# POWER.net
KiCad netlist of a schematic drawn in Altium Designer
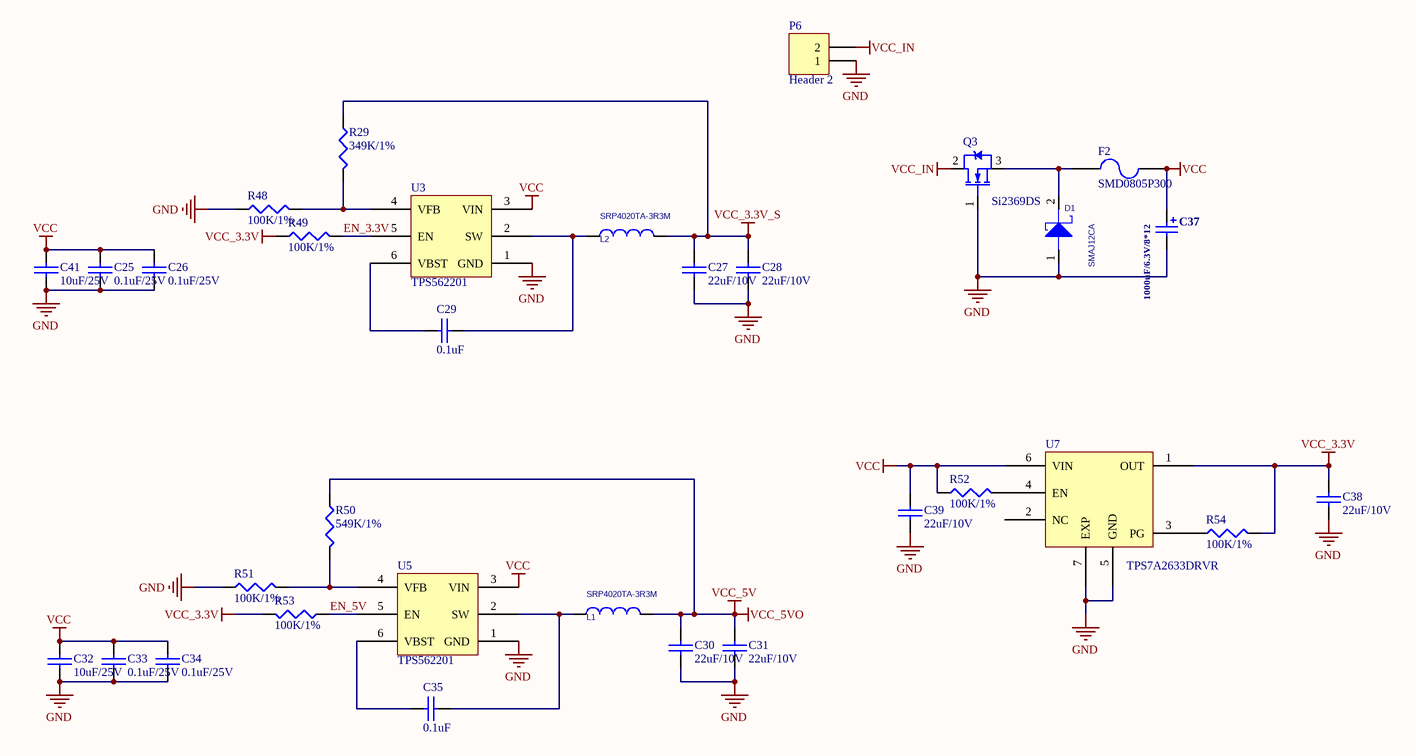
[diagram p0: POWER.SchDoc]

(export (version "E")
  (design (tool "Eeschema 10.0.6"))
  (components
    (comp (ref "C25")
      (value "0.1uF/25V")
      (footprint "0603C")
      (description "Capacitor")
      (libsource (lib "ZWLIntegrated_Library") (part "CAP"))
    )
    (comp (ref "C26")
      (value "0.1uF/25V")
      (footprint "0603C")
      (description "Capacitor")
      (libsource (lib "ZWLIntegrated_Library") (part "CAP"))
    )
    (comp (ref "C27")
      (value "22uF/10V")
      (footprint "1206C")
      (description "Capacitor")
      (libsource (lib "ZWLIntegrated_Library") (part "CAP"))
    )
    (comp (ref "C28")
      (value "22uF/10V")
      (footprint "1206C")
      (description "Capacitor")
      (libsource (lib "ZWLIntegrated_Library") (part "CAP"))
    )
    (comp (ref "C29")
      (value "0.1uF")
      (footprint "0603C")
      (description "Capacitor")
      (libsource (lib "ZWLIntegrated_Library") (part "CAP"))
    )
    (comp (ref "C30")
      (value "22uF/10V")
      (footprint "1206C")
      (description "Capacitor")
      (libsource (lib "ZWLIntegrated_Library") (part "CAP"))
    )
    (comp (ref "C31")
      (value "22uF/10V")
      (footprint "1206C")
      (description "Capacitor")
      (libsource (lib "ZWLIntegrated_Library") (part "CAP"))
    )
    (comp (ref "C32")
      (value "10uF/25V")
      (footprint "0603C")
      (description "Capacitor")
      (libsource (lib "ZWLIntegrated_Library") (part "CAP"))
    )
    (comp (ref "C33")
      (value "0.1uF/25V")
      (footprint "0603C")
      (description "Capacitor")
      (libsource (lib "ZWLIntegrated_Library") (part "CAP"))
    )
    (comp (ref "C34")
      (value "0.1uF/25V")
      (footprint "0603C")
      (description "Capacitor")
      (libsource (lib "ZWLIntegrated_Library") (part "CAP"))
    )
    (comp (ref "C35")
      (value "0.1uF")
      (footprint "0603C")
      (description "Capacitor")
      (libsource (lib "ZWLIntegrated_Library") (part "CAP"))
    )
    (comp (ref "C37")
      (value "1000uF/6.3V/8*12")
      (footprint "8*12")
      (description "Polarized Capacitor (Surface Mount)")
      (libsource (lib "KT_iBeacon") (part "Cap Pol3"))
    )
    (comp (ref "C38")
      (value "22uF/10V")
      (footprint "1206C")
      (description "Capacitor")
      (libsource (lib "ZWLIntegrated_Library") (part "CAP"))
    )
    (comp (ref "C39")
      (value "22uF/10V")
      (footprint "1206C")
      (description "Capacitor")
      (libsource (lib "ZWLIntegrated_Library") (part "CAP"))
    )
    (comp (ref "C41")
      (value "10uF/25V")
      (footprint "0603C")
      (description "Capacitor")
      (libsource (lib "ZWLIntegrated_Library") (part "CAP"))
    )
    (comp (ref "D1")
      (value "SMAJ12CA")
      (footprint "SMA")
      (libsource (lib "KT_iBeacon") (part "DIODE_SCHOTTKY_0"))
    )
    (comp (ref "F2")
      (value "SMD0805P300")
      (footprint "0805R")
      (description "Fuse")
      (fields (field (name "PUBLISHER") "Altium Limited"))
      (libsource (lib "Miscellaneous Devices") (part "Fuse 2"))
    )
    (comp (ref "L1") (value "SRP4020TA-3R3M") (footprint "CD_4*4") (libsource (lib "*") (part "INDUCTOR_1")))
    (comp (ref "L2") (value "SRP4020TA-3R3M") (footprint "CD_4*4") (libsource (lib "*") (part "INDUCTOR_1")))
    (comp (ref "P6")
      (value "Header 2")
      (footprint "2X2.54MMZ")
      (description "Header, 2-Pin")
      (fields (field (name "PUBLISHER") "Altium Limited"))
      (libsource (lib "Miscellaneous Connectors") (part "Header 2"))
    )
    (comp (ref "Q3")
      (value "Si2369DS")
      (footprint "sot23-3")
      (description "NMOSFET")
      (libsource (lib "SM") (part "NCE4060K"))
    )
    (comp (ref "R29")
      (value "349K/1%")
      (footprint "0603R")
      (libsource (lib "ZWLIntegrated_Library") (part "RES1"))
    )
    (comp (ref "R48")
      (value "100K/1%")
      (footprint "0603R")
      (libsource (lib "ZWLIntegrated_Library") (part "RES1"))
    )
    (comp (ref "R49")
      (value "100K/1%")
      (footprint "0603R")
      (libsource (lib "ZWLIntegrated_Library") (part "RES1"))
    )
    (comp (ref "R50")
      (value "549K/1%")
      (footprint "0603R")
      (libsource (lib "ZWLIntegrated_Library") (part "RES1"))
    )
    (comp (ref "R51")
      (value "100K/1%")
      (footprint "0603R")
      (libsource (lib "ZWLIntegrated_Library") (part "RES1"))
    )
    (comp (ref "R52")
      (value "100K/1%")
      (footprint "0603R")
      (libsource (lib "ZWLIntegrated_Library") (part "RES1"))
    )
    (comp (ref "R53")
      (value "100K/1%")
      (footprint "0603R")
      (libsource (lib "ZWLIntegrated_Library") (part "RES1"))
    )
    (comp (ref "R54")
      (value "100K/1%")
      (footprint "0603R")
      (libsource (lib "ZWLIntegrated_Library") (part "RES1"))
    )
    (comp (ref "U3")
      (value "TPS562201")
      (footprint "SOT-23-6")
      (libsource (lib "Schlib_20110825") (part "TPS562201"))
    )
    (comp (ref "U5")
      (value "TPS562201")
      (footprint "SOT-23-6")
      (libsource (lib "Schlib_20110825") (part "TPS562201"))
    )
    (comp (ref "U7")
      (value "TPS7A2633DRVR")
      (footprint "WSON-6")
      (libsource (lib "stm32") (part "TPS7A2633DRVR"))
    )
  )
  (nets
    (net (code "1") (name "/EN_3.3V") (class "Default")
      (node (ref "R49") (pin "2") (pinfunction "2_2") (pintype "passive"))
      (node (ref "U3") (pin "5") (pinfunction "EN_5") (pintype "passive"))
    )
    (net (code "2") (name "/EN_5V") (class "Default")
      (node (ref "R53") (pin "1") (pinfunction "1_1") (pintype "passive"))
      (node (ref "U5") (pin "5") (pinfunction "EN_5") (pintype "passive"))
    )
    (net (code "3") (name "GND") (class "Default")
      (node (ref "C25") (pin "1") (pinfunction "1_1") (pintype "passive"))
      (node (ref "C26") (pin "1") (pinfunction "1_1") (pintype "passive"))
      (node (ref "C27") (pin "2") (pinfunction "2_2") (pintype "passive"))
      (node (ref "C28") (pin "2") (pinfunction "2_2") (pintype "passive"))
      (node (ref "C30") (pin "2") (pinfunction "2_2") (pintype "passive"))
      (node (ref "C31") (pin "2") (pinfunction "2_2") (pintype "passive"))
      (node (ref "C32") (pin "1") (pinfunction "1_1") (pintype "passive"))
      (node (ref "C33") (pin "1") (pinfunction "1_1") (pintype "passive"))
      (node (ref "C34") (pin "1") (pinfunction "1_1") (pintype "passive"))
      (node (ref "C37") (pin "2") (pinfunction "2_2") (pintype "passive"))
      (node (ref "C38") (pin "2") (pinfunction "2_2") (pintype "passive"))
      (node (ref "C39") (pin "2") (pinfunction "2_2") (pintype "passive"))
      (node (ref "C41") (pin "1") (pinfunction "1_1") (pintype "passive"))
      (node (ref "D1") (pin "1") (pinfunction "1_1") (pintype "passive"))
      (node (ref "P6") (pin "1") (pinfunction "1_1") (pintype "passive"))
      (node (ref "Q3") (pin "1") (pinfunction "G_1") (pintype "passive"))
      (node (ref "R48") (pin "1") (pinfunction "1_1") (pintype "passive"))
      (node (ref "R51") (pin "1") (pinfunction "1_1") (pintype "passive"))
      (node (ref "U3") (pin "1") (pinfunction "GND_1") (pintype "passive"))
      (node (ref "U5") (pin "1") (pinfunction "GND_1") (pintype "passive"))
      (node (ref "U7") (pin "5") (pinfunction "GND_5") (pintype "passive"))
      (node (ref "U7") (pin "7") (pinfunction "EXP_7") (pintype "passive"))
    )
    (net (code "4") (name "Net-(Q3-S)") (class "Default")
      (node (ref "D1") (pin "2") (pinfunction "2_2") (pintype "passive"))
      (node (ref "F2") (pin "1") (pinfunction "1_1") (pintype "passive"))
      (node (ref "Q3") (pin "3") (pinfunction "S_3") (pintype "passive"))
    )
    (net (code "5") (name "Net-(U3-SW)") (class "Default")
      (node (ref "C29") (pin "1") (pinfunction "1_1") (pintype "passive"))
      (node (ref "L2") (pin "1") (pinfunction "1_1") (pintype "passive"))
      (node (ref "U3") (pin "2") (pinfunction "SW_2") (pintype "passive"))
    )
    (net (code "6") (name "Net-(U3-VBST)") (class "Default")
      (node (ref "C29") (pin "2") (pinfunction "2_2") (pintype "passive"))
      (node (ref "U3") (pin "6") (pinfunction "VBST_6") (pintype "passive"))
    )
    (net (code "7") (name "Net-(U3-VFB)") (class "Default")
      (node (ref "R29") (pin "2") (pinfunction "2_2") (pintype "passive"))
      (node (ref "R48") (pin "2") (pinfunction "2_2") (pintype "passive"))
      (node (ref "U3") (pin "4") (pinfunction "VFB_4") (pintype "passive"))
    )
    (net (code "8") (name "Net-(U5-SW)") (class "Default")
      (node (ref "C35") (pin "1") (pinfunction "1_1") (pintype "passive"))
      (node (ref "L1") (pin "1") (pinfunction "1_1") (pintype "passive"))
      (node (ref "U5") (pin "2") (pinfunction "SW_2") (pintype "passive"))
    )
    (net (code "9") (name "Net-(U5-VBST)") (class "Default")
      (node (ref "C35") (pin "2") (pinfunction "2_2") (pintype "passive"))
      (node (ref "U5") (pin "6") (pinfunction "VBST_6") (pintype "passive"))
    )
    (net (code "10") (name "Net-(U5-VFB)") (class "Default")
      (node (ref "R50") (pin "2") (pinfunction "2_2") (pintype "passive"))
      (node (ref "R51") (pin "2") (pinfunction "2_2") (pintype "passive"))
      (node (ref "U5") (pin "4") (pinfunction "VFB_4") (pintype "passive"))
    )
    (net (code "11") (name "Net-(U7-EN)") (class "Default")
      (node (ref "R52") (pin "2") (pinfunction "2_2") (pintype "passive"))
      (node (ref "U7") (pin "4") (pinfunction "EN_4") (pintype "passive"))
    )
    (net (code "12") (name "Net-(U7-PG)") (class "Default")
      (node (ref "R54") (pin "1") (pinfunction "1_1") (pintype "passive"))
      (node (ref "U7") (pin "3") (pinfunction "PG_3") (pintype "passive"))
    )
    (net (code "13") (name "VCC") (class "Default")
      (node (ref "C25") (pin "2") (pinfunction "2_2") (pintype "passive"))
      (node (ref "C26") (pin "2") (pinfunction "2_2") (pintype "passive"))
      (node (ref "C32") (pin "2") (pinfunction "2_2") (pintype "passive"))
      (node (ref "C33") (pin "2") (pinfunction "2_2") (pintype "passive"))
      (node (ref "C34") (pin "2") (pinfunction "2_2") (pintype "passive"))
      (node (ref "C37") (pin "1") (pinfunction "1_1") (pintype "passive"))
      (node (ref "C39") (pin "1") (pinfunction "1_1") (pintype "passive"))
      (node (ref "C41") (pin "2") (pinfunction "2_2") (pintype "passive"))
      (node (ref "F2") (pin "2") (pinfunction "2_2") (pintype "passive"))
      (node (ref "R52") (pin "1") (pinfunction "1_1") (pintype "passive"))
      (node (ref "U3") (pin "3") (pinfunction "VIN_3") (pintype "passive"))
      (node (ref "U5") (pin "3") (pinfunction "VIN_3") (pintype "passive"))
      (node (ref "U7") (pin "6") (pinfunction "VIN_6") (pintype "passive"))
    )
    (net (code "14") (name "VCC_3.3V") (class "Default")
      (node (ref "C38") (pin "1") (pinfunction "1_1") (pintype "passive"))
      (node (ref "R49") (pin "1") (pinfunction "1_1") (pintype "passive"))
      (node (ref "R53") (pin "2") (pinfunction "2_2") (pintype "passive"))
      (node (ref "R54") (pin "2") (pinfunction "2_2") (pintype "passive"))
      (node (ref "U7") (pin "1") (pinfunction "OUT_1") (pintype "passive"))
    )
    (net (code "15") (name "VCC_3.3V_S") (class "Default")
      (node (ref "C27") (pin "1") (pinfunction "1_1") (pintype "passive"))
      (node (ref "C28") (pin "1") (pinfunction "1_1") (pintype "passive"))
      (node (ref "L2") (pin "2") (pinfunction "2_2") (pintype "passive"))
      (node (ref "R29") (pin "1") (pinfunction "1_1") (pintype "passive"))
    )
    (net (code "16") (name "VCC_5V") (class "Default")
      (node (ref "C30") (pin "1") (pinfunction "1_1") (pintype "passive"))
      (node (ref "C31") (pin "1") (pinfunction "1_1") (pintype "passive"))
      (node (ref "L1") (pin "2") (pinfunction "2_2") (pintype "passive"))
      (node (ref "R50") (pin "1") (pinfunction "1_1") (pintype "passive"))
    )
    (net (code "17") (name "VCC_IN") (class "Default")
      (node (ref "P6") (pin "2") (pinfunction "2_2") (pintype "passive"))
      (node (ref "Q3") (pin "2") (pinfunction "D_2") (pintype "passive"))
    )
    (net (code "18") (name "unconnected-(U7-NC-Pad2)") (class "Default")
      (node (ref "U7") (pin "2") (pinfunction "NC_2") (pintype "passive"))
    )
  )
)
